# X_Axis_Stepper_Motor_Driver.net
KiCad netlist of a schematic drawn in Altium Designer
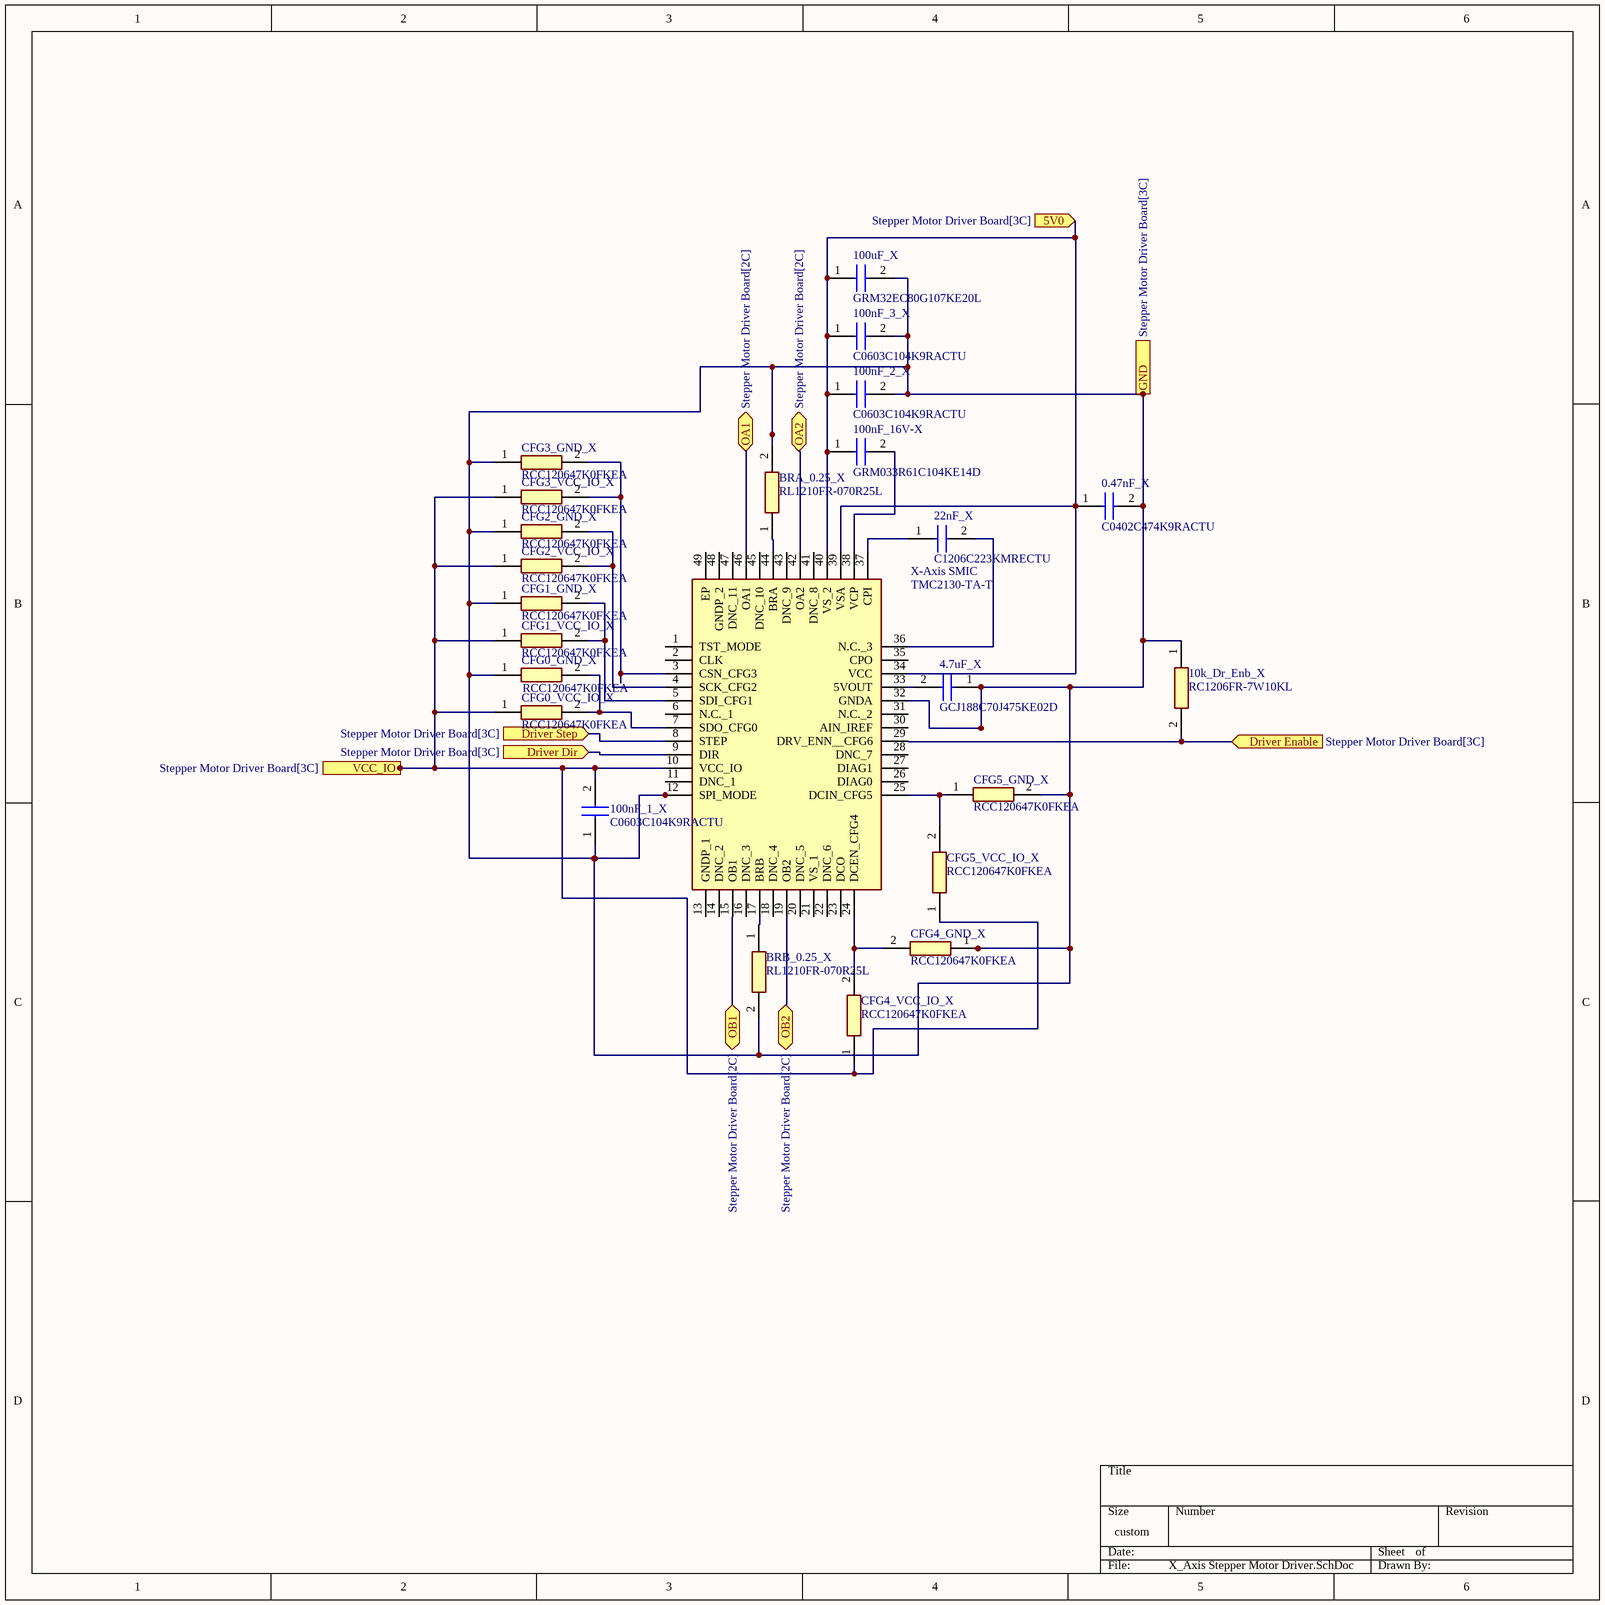
[diagram p0: X_Axis Stepper Motor Driver.SchDoc]

(export (version "E")
  (design (tool "Eeschema 10.0.6"))
  (components
    (comp (ref "0.47nF_X")
      (value "C0402C474K9RACTU")
      (footprint "SamacSys:CAPC1005X55N")
      (description "Capacitor")
      (fields (field (name "MOUSER PART NUMBER") "80-C0402C474K9RACTU"))
      (libsource (lib "*") (part "C0402C474K9RACTU"))
    )
    (comp (ref "4.7uF_X")
      (value "GCJ188C70J475KE02D")
      (footprint "SamacSys:CAPC1608X100N")
      (description "Capacitor")
      (fields (field (name "MOUSER PART NUMBER") "81-GCJ188C70J475KE2D"))
      (libsource (lib "*") (part "GCJ188C70J475KE02D"))
    )
    (comp (ref "10k_Dr_Enb_X")
      (value "RC1206FR-7W10KL")
      (footprint "SamacSys:RESC3116X65N")
      (description "Resistor")
      (libsource (lib "*") (part "RC1206FR-7W10KL"))
    )
    (comp (ref "22nF_X")
      (value "C1206C223KMRECTU")
      (footprint "SamacSys:C1206")
      (description "Capacitor")
      (fields (field (name "MOUSER PART NUMBER") "80-C1206C223KMRECTU"))
      (libsource (lib "*") (part "C1206C223KMRECTU"))
    )
    (comp (ref "100nF_1_X")
      (value "C0603C104K9RACTU")
      (footprint "SamacSys:C0603")
      (description "Capacitor")
      (fields (field (name "MOUSER PART NUMBER") "80-C0603C104K9R"))
      (libsource (lib "*") (part "C0603C104K9RACTU"))
    )
    (comp (ref "100nF_2_X")
      (value "C0603C104K9RACTU")
      (footprint "SamacSys:C0603")
      (description "Capacitor")
      (fields (field (name "MOUSER PART NUMBER") "80-C0603C104K9R"))
      (libsource (lib "*") (part "C0603C104K9RACTU"))
    )
    (comp (ref "100nF_3_X")
      (value "C0603C104K9RACTU")
      (footprint "SamacSys:C0603")
      (description "Capacitor")
      (fields (field (name "MOUSER PART NUMBER") "80-C0603C104K9R"))
      (libsource (lib "*") (part "C0603C104K9RACTU"))
    )
    (comp (ref "100nF_16V-X")
      (value "GRM033R61C104KE14D")
      (footprint "SamacSys:CAPC0603X33N")
      (description "Capacitor")
      (fields (field (name "MOUSER PART NUMBER") "81-GRM033R61C104KE4D"))
      (libsource (lib "*") (part "GRM033R61C104KE14D"))
    )
    (comp (ref "100uF_X")
      (value "GRM32EC80G107KE20L")
      (footprint "SamacSys:CAPC3225X270N")
      (description "Capacitor")
      (fields (field (name "MOUSER PART NUMBER") "81-GRM32EC80G107KE0L"))
      (libsource (lib "*") (part "GRM32EC80G107KE20L"))
    )
    (comp (ref "BRA_0.25_X")
      (value "RL1210FR-070R25L")
      (footprint "SamacSys:RESC3126X65N")
      (description "Resistor")
      (fields (field (name "MOUSER PART NUMBER") "603-RL1210FR-070R25L"))
      (libsource (lib "*") (part "RL1210FR-070R25L"))
    )
    (comp (ref "BRB_0.25_X")
      (value "RL1210FR-070R25L")
      (footprint "SamacSys:RESC3126X65N")
      (description "Resistor")
      (fields (field (name "MOUSER PART NUMBER") "603-RL1210FR-070R25L"))
      (libsource (lib "") (part "RL1210FR-070R25L_1"))
    )
    (comp (ref "CFG0_GND_X")
      (value "RCC120647K0FKEA")
      (footprint "SamacSys:RCC1206_e3")
      (description "Resistor")
      (fields (field (name "MOUSER PART NUMBER") "71-RCC120647K0FKEA"))
      (libsource (lib "*") (part "RCC120647K0FKEA"))
    )
    (comp (ref "CFG0_VCC_IO_X")
      (value "RCC120647K0FKEA")
      (footprint "SamacSys:RCC1206_e3")
      (description "Resistor")
      (fields (field (name "MOUSER PART NUMBER") "71-RCC120647K0FKEA"))
      (libsource (lib "*") (part "RCC120647K0FKEA"))
    )
    (comp (ref "CFG1_GND_X")
      (value "RCC120647K0FKEA")
      (footprint "SamacSys:RCC1206_e3")
      (description "Resistor")
      (fields (field (name "MOUSER PART NUMBER") "71-RCC120647K0FKEA"))
      (libsource (lib "*") (part "RCC120647K0FKEA"))
    )
    (comp (ref "CFG1_VCC_IO_X")
      (value "RCC120647K0FKEA")
      (footprint "SamacSys:RCC1206_e3")
      (description "Resistor")
      (fields (field (name "MOUSER PART NUMBER") "71-RCC120647K0FKEA"))
      (libsource (lib "*") (part "RCC120647K0FKEA"))
    )
    (comp (ref "CFG2_GND_X")
      (value "RCC120647K0FKEA")
      (footprint "SamacSys:RCC1206_e3")
      (description "Resistor")
      (fields (field (name "MOUSER PART NUMBER") "71-RCC120647K0FKEA"))
      (libsource (lib "*") (part "RCC120647K0FKEA"))
    )
    (comp (ref "CFG2_VCC_IO_X")
      (value "RCC120647K0FKEA")
      (footprint "SamacSys:RCC1206_e3")
      (description "Resistor")
      (fields (field (name "MOUSER PART NUMBER") "71-RCC120647K0FKEA"))
      (libsource (lib "*") (part "RCC120647K0FKEA"))
    )
    (comp (ref "CFG3_GND_X")
      (value "RCC120647K0FKEA")
      (footprint "SamacSys:RCC1206_e3")
      (description "Resistor")
      (fields (field (name "MOUSER PART NUMBER") "71-RCC120647K0FKEA"))
      (libsource (lib "*") (part "RCC120647K0FKEA"))
    )
    (comp (ref "CFG3_VCC_IO_X")
      (value "RCC120647K0FKEA")
      (footprint "SamacSys:RCC1206_e3")
      (description "Resistor")
      (fields (field (name "MOUSER PART NUMBER") "71-RCC120647K0FKEA"))
      (libsource (lib "*") (part "RCC120647K0FKEA"))
    )
    (comp (ref "CFG4_GND_X")
      (value "RCC120647K0FKEA")
      (footprint "SamacSys:RCC1206_e3")
      (description "Resistor")
      (fields (field (name "MOUSER PART NUMBER") "71-RCC120647K0FKEA"))
      (libsource (lib "") (part "RCC120647K0FKEA_1"))
    )
    (comp (ref "CFG4_VCC_IO_X")
      (value "RCC120647K0FKEA")
      (footprint "SamacSys:RCC1206_e3")
      (description "Resistor")
      (fields (field (name "MOUSER PART NUMBER") "71-RCC120647K0FKEA"))
      (libsource (lib "") (part "RCC120647K0FKEA_2"))
    )
    (comp (ref "CFG5_GND_X")
      (value "RCC120647K0FKEA")
      (footprint "SamacSys:RCC1206_e3")
      (description "Resistor")
      (fields (field (name "MOUSER PART NUMBER") "71-RCC120647K0FKEA"))
      (libsource (lib "*") (part "RCC120647K0FKEA"))
    )
    (comp (ref "CFG5_VCC_IO_X")
      (value "RCC120647K0FKEA")
      (footprint "SamacSys:RCC1206_e3")
      (description "Resistor")
      (fields (field (name "MOUSER PART NUMBER") "71-RCC120647K0FKEA"))
      (libsource (lib "") (part "RCC120647K0FKEA_2"))
    )
    (comp (ref "X-Axis SMIC")
      (value "TMC2130-TA-T")
      (footprint "SamacSys:QFP50P900X900X120-49N")
      (description "Integrated Circuit")
      (fields (field (name "MOUSER PART NUMBER") "700-TMC2130-TA-T"))
      (libsource (lib "*") (part "TMC2130-TA-T"))
    )
  )
  (nets
    (net (code "1") (name "/5V0") (class "Default")
      (node (ref "0.47nF_X") (pin "1") (pinfunction "1_1") (pintype "passive"))
      (node (ref "100nF_16V-X") (pin "1") (pinfunction "1_1") (pintype "passive"))
      (node (ref "100nF_2_X") (pin "1") (pinfunction "1_1") (pintype "passive"))
      (node (ref "100nF_3_X") (pin "1") (pinfunction "1_1") (pintype "passive"))
      (node (ref "100uF_X") (pin "1") (pinfunction "1_1") (pintype "passive"))
      (node (ref "X-Axis SMIC") (pin "34") (pinfunction "VCC_34") (pintype "passive"))
      (node (ref "X-Axis SMIC") (pin "39") (pinfunction "VSA_39") (pintype "passive"))
      (node (ref "X-Axis SMIC") (pin "40") (pinfunction "VS_2_40") (pintype "passive"))
    )
    (net (code "2") (name "/Driver Dir") (class "Default")
      (node (ref "X-Axis SMIC") (pin "9") (pinfunction "DIR_9") (pintype "passive"))
    )
    (net (code "3") (name "/Driver Enable") (class "Default")
      (node (ref "10k_Dr_Enb_X") (pin "2") (pinfunction "2_2") (pintype "passive"))
      (node (ref "X-Axis SMIC") (pin "29") (pinfunction "DRV_ENN__CFG6_29") (pintype "passive"))
    )
    (net (code "4") (name "/Driver Step") (class "Default")
      (node (ref "X-Axis SMIC") (pin "8") (pinfunction "STEP_8") (pintype "passive"))
    )
    (net (code "5") (name "/GND") (class "Default")
      (node (ref "0.47nF_X") (pin "2") (pinfunction "2_2") (pintype "passive"))
      (node (ref "100nF_1_X") (pin "1") (pinfunction "1_1") (pintype "passive"))
      (node (ref "100nF_2_X") (pin "2") (pinfunction "2_2") (pintype "passive"))
      (node (ref "100nF_3_X") (pin "2") (pinfunction "2_2") (pintype "passive"))
      (node (ref "100uF_X") (pin "2") (pinfunction "2_2") (pintype "passive"))
      (node (ref "10k_Dr_Enb_X") (pin "1") (pinfunction "1_1") (pintype "passive"))
      (node (ref "4.7uF_X") (pin "1") (pinfunction "1_1") (pintype "passive"))
      (node (ref "BRA_0.25_X") (pin "2") (pinfunction "2_2") (pintype "passive"))
      (node (ref "BRB_0.25_X") (pin "2") (pinfunction "2_2") (pintype "passive"))
      (node (ref "CFG0_GND_X") (pin "1") (pinfunction "1_1") (pintype "passive"))
      (node (ref "CFG1_GND_X") (pin "1") (pinfunction "1_1") (pintype "passive"))
      (node (ref "CFG2_GND_X") (pin "1") (pinfunction "1_1") (pintype "passive"))
      (node (ref "CFG3_GND_X") (pin "1") (pinfunction "1_1") (pintype "passive"))
      (node (ref "CFG4_GND_X") (pin "1") (pinfunction "1_1") (pintype "passive"))
      (node (ref "CFG5_GND_X") (pin "2") (pinfunction "2_2") (pintype "passive"))
      (node (ref "X-Axis SMIC") (pin "12") (pinfunction "SPI_MODE_12") (pintype "passive"))
      (node (ref "X-Axis SMIC") (pin "32") (pinfunction "GNDA_32") (pintype "passive"))
    )
    (net (code "6") (name "/OA1") (class "Default")
      (node (ref "X-Axis SMIC") (pin "46") (pinfunction "OA1_46") (pintype "passive"))
    )
    (net (code "7") (name "/OA2") (class "Default")
      (node (ref "X-Axis SMIC") (pin "42") (pinfunction "OA2_42") (pintype "passive"))
    )
    (net (code "8") (name "/OB1") (class "Default")
      (node (ref "X-Axis SMIC") (pin "15") (pinfunction "OB1_15") (pintype "passive"))
    )
    (net (code "9") (name "/OB2") (class "Default")
      (node (ref "X-Axis SMIC") (pin "19") (pinfunction "OB2_19") (pintype "passive"))
    )
    (net (code "10") (name "/VCC_IO") (class "Default")
      (node (ref "100nF_1_X") (pin "2") (pinfunction "2_2") (pintype "passive"))
      (node (ref "CFG0_VCC_IO_X") (pin "1") (pinfunction "1_1") (pintype "passive"))
      (node (ref "CFG1_VCC_IO_X") (pin "1") (pinfunction "1_1") (pintype "passive"))
      (node (ref "CFG2_VCC_IO_X") (pin "1") (pinfunction "1_1") (pintype "passive"))
      (node (ref "CFG3_VCC_IO_X") (pin "1") (pinfunction "1_1") (pintype "passive"))
      (node (ref "CFG4_VCC_IO_X") (pin "1") (pinfunction "1_1") (pintype "passive"))
      (node (ref "CFG5_VCC_IO_X") (pin "1") (pinfunction "1_1") (pintype "passive"))
      (node (ref "X-Axis SMIC") (pin "10") (pinfunction "VCC_IO_10") (pintype "passive"))
    )
    (net (code "11") (name "Net-(X-Axis SMIC-5VOUT)") (class "Default")
      (node (ref "4.7uF_X") (pin "2") (pinfunction "2_2") (pintype "passive"))
      (node (ref "X-Axis SMIC") (pin "33") (pinfunction "5VOUT_33") (pintype "passive"))
    )
    (net (code "12") (name "Net-(X-Axis SMIC-BRA)") (class "Default")
      (node (ref "BRA_0.25_X") (pin "1") (pinfunction "1_1") (pintype "passive"))
      (node (ref "X-Axis SMIC") (pin "44") (pinfunction "BRA_44") (pintype "passive"))
    )
    (net (code "13") (name "Net-(X-Axis SMIC-BRB)") (class "Default")
      (node (ref "BRB_0.25_X") (pin "1") (pinfunction "1_1") (pintype "passive"))
      (node (ref "X-Axis SMIC") (pin "17") (pinfunction "BRB_17") (pintype "passive"))
    )
    (net (code "14") (name "Net-(X-Axis SMIC-CPI)") (class "Default")
      (node (ref "22nF_X") (pin "1") (pinfunction "1_1") (pintype "passive"))
      (node (ref "X-Axis SMIC") (pin "37") (pinfunction "CPI_37") (pintype "passive"))
    )
    (net (code "15") (name "Net-(X-Axis SMIC-CSN_CFG3)") (class "Default")
      (node (ref "CFG3_GND_X") (pin "2") (pinfunction "2_2") (pintype "passive"))
      (node (ref "CFG3_VCC_IO_X") (pin "2") (pinfunction "2_2") (pintype "passive"))
      (node (ref "X-Axis SMIC") (pin "3") (pinfunction "CSN_CFG3_3") (pintype "passive"))
    )
    (net (code "16") (name "Net-(X-Axis SMIC-DCEN_CFG4)") (class "Default")
      (node (ref "CFG4_GND_X") (pin "2") (pinfunction "2_2") (pintype "passive"))
      (node (ref "CFG4_VCC_IO_X") (pin "2") (pinfunction "2_2") (pintype "passive"))
      (node (ref "X-Axis SMIC") (pin "24") (pinfunction "DCEN_CFG4_24") (pintype "passive"))
    )
    (net (code "17") (name "Net-(X-Axis SMIC-DCIN_CFG5)") (class "Default")
      (node (ref "CFG5_GND_X") (pin "1") (pinfunction "1_1") (pintype "passive"))
      (node (ref "CFG5_VCC_IO_X") (pin "2") (pinfunction "2_2") (pintype "passive"))
      (node (ref "X-Axis SMIC") (pin "25") (pinfunction "DCIN_CFG5_25") (pintype "passive"))
    )
    (net (code "18") (name "Net-(X-Axis SMIC-N.C._3)") (class "Default")
      (node (ref "22nF_X") (pin "2") (pinfunction "2_2") (pintype "passive"))
      (node (ref "X-Axis SMIC") (pin "36") (pinfunction "N.C._3_36") (pintype "passive"))
    )
    (net (code "19") (name "Net-(X-Axis SMIC-SCK_CFG2)") (class "Default")
      (node (ref "CFG2_GND_X") (pin "2") (pinfunction "2_2") (pintype "passive"))
      (node (ref "CFG2_VCC_IO_X") (pin "2") (pinfunction "2_2") (pintype "passive"))
      (node (ref "X-Axis SMIC") (pin "4") (pinfunction "SCK_CFG2_4") (pintype "passive"))
    )
    (net (code "20") (name "Net-(X-Axis SMIC-SDI_CFG1)") (class "Default")
      (node (ref "CFG1_GND_X") (pin "2") (pinfunction "2_2") (pintype "passive"))
      (node (ref "CFG1_VCC_IO_X") (pin "2") (pinfunction "2_2") (pintype "passive"))
      (node (ref "X-Axis SMIC") (pin "5") (pinfunction "SDI_CFG1_5") (pintype "passive"))
    )
    (net (code "21") (name "Net-(X-Axis SMIC-SDO_CFG0)") (class "Default")
      (node (ref "CFG0_GND_X") (pin "2") (pinfunction "2_2") (pintype "passive"))
      (node (ref "CFG0_VCC_IO_X") (pin "2") (pinfunction "2_2") (pintype "passive"))
      (node (ref "X-Axis SMIC") (pin "7") (pinfunction "SDO_CFG0_7") (pintype "passive"))
    )
    (net (code "22") (name "Net-(X-Axis SMIC-VCP)") (class "Default")
      (node (ref "100nF_16V-X") (pin "2") (pinfunction "2_2") (pintype "passive"))
      (node (ref "X-Axis SMIC") (pin "38") (pinfunction "VCP_38") (pintype "passive"))
    )
    (net (code "23") (name "unconnected-(X-Axis SMIC-AIN_IREF-Pad30)") (class "Default")
      (node (ref "X-Axis SMIC") (pin "30") (pinfunction "AIN_IREF_30") (pintype "passive"))
    )
    (net (code "24") (name "unconnected-(X-Axis SMIC-CLK-Pad2)") (class "Default")
      (node (ref "X-Axis SMIC") (pin "2") (pinfunction "CLK_2") (pintype "passive"))
    )
    (net (code "25") (name "unconnected-(X-Axis SMIC-CPO-Pad35)") (class "Default")
      (node (ref "X-Axis SMIC") (pin "35") (pinfunction "CPO_35") (pintype "passive"))
    )
    (net (code "26") (name "unconnected-(X-Axis SMIC-DCO-Pad23)") (class "Default")
      (node (ref "X-Axis SMIC") (pin "23") (pinfunction "DCO_23") (pintype "passive"))
    )
    (net (code "27") (name "unconnected-(X-Axis SMIC-DIAG0-Pad26)") (class "Default")
      (node (ref "X-Axis SMIC") (pin "26") (pinfunction "DIAG0_26") (pintype "passive"))
    )
    (net (code "28") (name "unconnected-(X-Axis SMIC-DIAG1-Pad27)") (class "Default")
      (node (ref "X-Axis SMIC") (pin "27") (pinfunction "DIAG1_27") (pintype "passive"))
    )
    (net (code "29") (name "unconnected-(X-Axis SMIC-DNC_1-Pad11)") (class "Default")
      (node (ref "X-Axis SMIC") (pin "11") (pinfunction "DNC_1_11") (pintype "passive"))
    )
    (net (code "30") (name "unconnected-(X-Axis SMIC-DNC_2-Pad14)") (class "Default")
      (node (ref "X-Axis SMIC") (pin "14") (pinfunction "DNC_2_14") (pintype "passive"))
    )
    (net (code "31") (name "unconnected-(X-Axis SMIC-DNC_3-Pad16)") (class "Default")
      (node (ref "X-Axis SMIC") (pin "16") (pinfunction "DNC_3_16") (pintype "passive"))
    )
    (net (code "32") (name "unconnected-(X-Axis SMIC-DNC_4-Pad18)") (class "Default")
      (node (ref "X-Axis SMIC") (pin "18") (pinfunction "DNC_4_18") (pintype "passive"))
    )
    (net (code "33") (name "unconnected-(X-Axis SMIC-DNC_5-Pad20)") (class "Default")
      (node (ref "X-Axis SMIC") (pin "20") (pinfunction "DNC_5_20") (pintype "passive"))
    )
    (net (code "34") (name "unconnected-(X-Axis SMIC-DNC_6-Pad22)") (class "Default")
      (node (ref "X-Axis SMIC") (pin "22") (pinfunction "DNC_6_22") (pintype "passive"))
    )
    (net (code "35") (name "unconnected-(X-Axis SMIC-DNC_7-Pad28)") (class "Default")
      (node (ref "X-Axis SMIC") (pin "28") (pinfunction "DNC_7_28") (pintype "passive"))
    )
    (net (code "36") (name "unconnected-(X-Axis SMIC-DNC_8-Pad41)") (class "Default")
      (node (ref "X-Axis SMIC") (pin "41") (pinfunction "DNC_8_41") (pintype "passive"))
    )
    (net (code "37") (name "unconnected-(X-Axis SMIC-DNC_9-Pad43)") (class "Default")
      (node (ref "X-Axis SMIC") (pin "43") (pinfunction "DNC_9_43") (pintype "passive"))
    )
    (net (code "38") (name "unconnected-(X-Axis SMIC-DNC_10-Pad45)") (class "Default")
      (node (ref "X-Axis SMIC") (pin "45") (pinfunction "DNC_10_45") (pintype "passive"))
    )
    (net (code "39") (name "unconnected-(X-Axis SMIC-DNC_11-Pad47)") (class "Default")
      (node (ref "X-Axis SMIC") (pin "47") (pinfunction "DNC_11_47") (pintype "passive"))
    )
    (net (code "40") (name "unconnected-(X-Axis SMIC-EP-Pad49)") (class "Default")
      (node (ref "X-Axis SMIC") (pin "49") (pinfunction "EP_49") (pintype "passive"))
    )
    (net (code "41") (name "unconnected-(X-Axis SMIC-GNDP_1-Pad13)") (class "Default")
      (node (ref "X-Axis SMIC") (pin "13") (pinfunction "GNDP_1_13") (pintype "passive"))
    )
    (net (code "42") (name "unconnected-(X-Axis SMIC-GNDP_2-Pad48)") (class "Default")
      (node (ref "X-Axis SMIC") (pin "48") (pinfunction "GNDP_2_48") (pintype "passive"))
    )
    (net (code "43") (name "unconnected-(X-Axis SMIC-N.C._1-Pad6)") (class "Default")
      (node (ref "X-Axis SMIC") (pin "6") (pinfunction "N.C._1_6") (pintype "passive"))
    )
    (net (code "44") (name "unconnected-(X-Axis SMIC-N.C._2-Pad31)") (class "Default")
      (node (ref "X-Axis SMIC") (pin "31") (pinfunction "N.C._2_31") (pintype "passive"))
    )
    (net (code "45") (name "unconnected-(X-Axis SMIC-TST_MODE-Pad1)") (class "Default")
      (node (ref "X-Axis SMIC") (pin "1") (pinfunction "TST_MODE_1") (pintype "passive"))
    )
    (net (code "46") (name "unconnected-(X-Axis SMIC-VS_1-Pad21)") (class "Default")
      (node (ref "X-Axis SMIC") (pin "21") (pinfunction "VS_1_21") (pintype "passive"))
    )
  )
)
